# 3310USBC-1.net
KiCad netlist of a schematic drawn in EasyEDA Pro
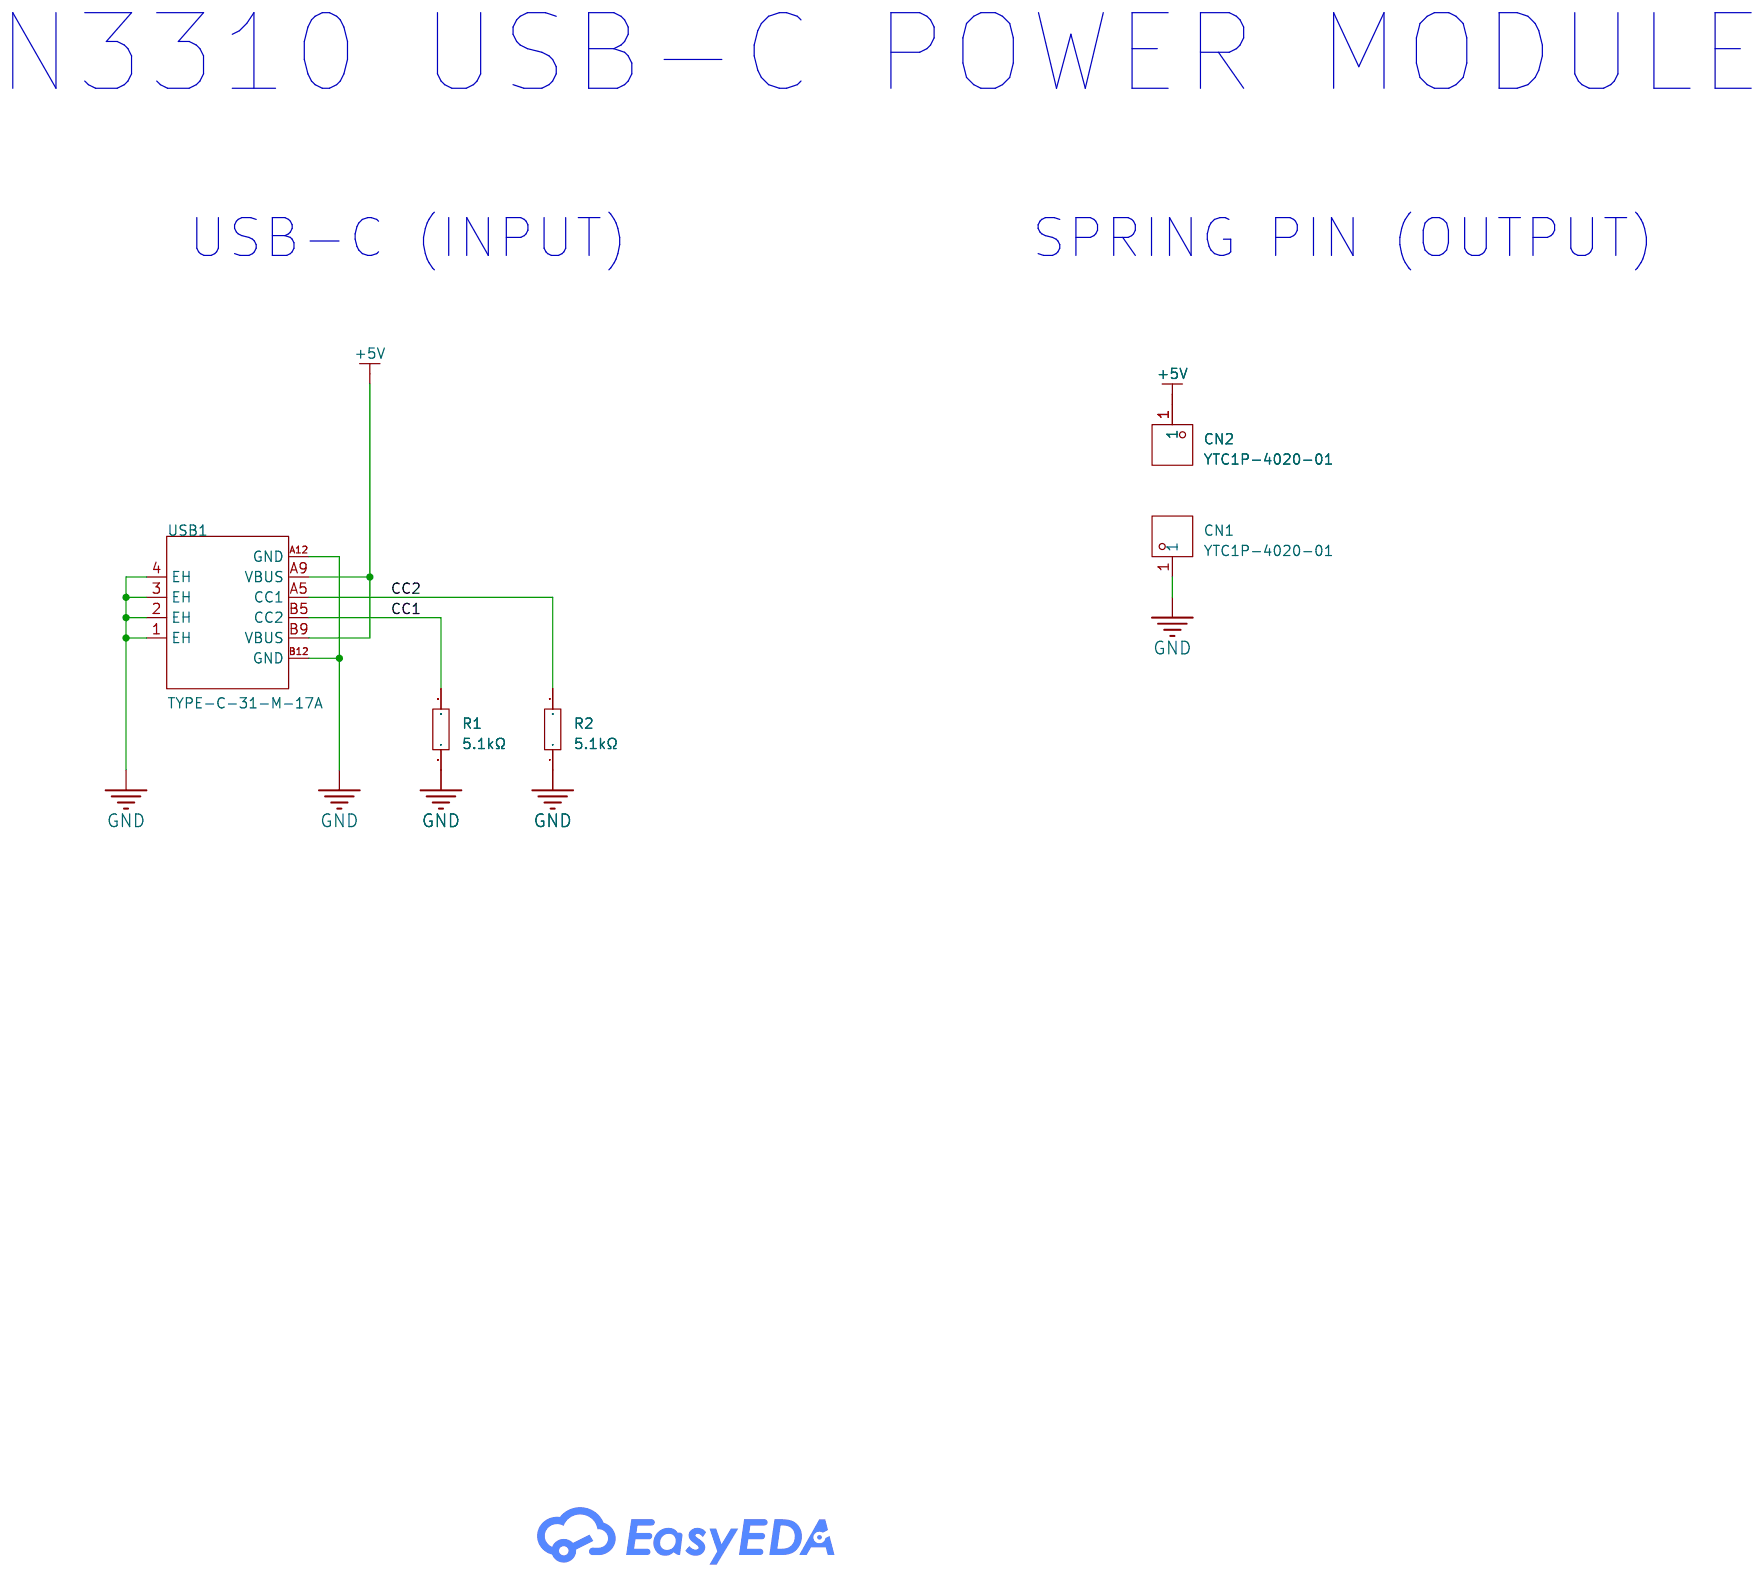
[diagram p0: schematic sheet]

(export (version "E")
  (design (tool "Eeschema 10.0.6"))
  (components
    (comp (ref "CN1")
      (value "YTC1P-4020-01")
      (footprint "easyedapro:TESTPOINT-SMD_BD2.0_YTC1P-4020-01")
      (fields (field (name "Manufacturer") "YIYUAN(怡远)"))
      (libsource (lib "easyedapro") (part "YTC1P-4020-01"))
    )
    (comp (ref "CN2")
      (value "YTC1P-4020-01")
      (footprint "easyedapro:TESTPOINT-SMD_BD2.0_YTC1P-4020-01")
      (fields (field (name "Manufacturer") "YIYUAN(怡远)"))
      (libsource (lib "easyedapro") (part "YTC1P-4020-01"))
    )
    (comp (ref "R1")
      (value "5.1kΩ")
      (footprint "easyedapro:R0805")
      (fields
        (field (name "Manufacturer Part") "0805W8F5101T5E")
        (field (name "Manufacturer") "UNI-ROYAL(厚声)")
      )
      (libsource (lib "easyedapro") (part "0805W8F5101T5E"))
    )
    (comp (ref "R2")
      (value "5.1kΩ")
      (footprint "easyedapro:R0805")
      (fields
        (field (name "Manufacturer Part") "0805W8F5101T5E")
        (field (name "Manufacturer") "UNI-ROYAL(厚声)")
      )
      (libsource (lib "easyedapro") (part "0805W8F5101T5E"))
    )
    (comp (ref "USB1")
      (value "TYPE-C-31-M-17A")
      (footprint "easyedapro:TYPE-C-SMD_TYPE-C-31-M-17A")
      (fields (field (name "Manufacturer") "韩国韩荣"))
      (libsource (lib "easyedapro") (part "TYPE-C-31-M-17A"))
    )
  )
  (nets
    (net (code "1") (name "+5V") (class "Default")
      (node (ref "CN2") (pin "1") (pinfunction "1_1") (pintype "unspecified"))
      (node (ref "USB1") (pin "A9") (pinfunction "VBUS_A9") (pintype "unspecified"))
      (node (ref "USB1") (pin "B9") (pinfunction "VBUS_B9") (pintype "unspecified"))
    )
    (net (code "2") (name "/CC1") (class "Default")
      (node (ref "R1") (pin "2") (pinfunction "2_2") (pintype "input"))
      (node (ref "USB1") (pin "B5") (pinfunction "CC2_B5") (pintype "unspecified"))
    )
    (net (code "3") (name "/CC2") (class "Default")
      (node (ref "R2") (pin "2") (pinfunction "2_2") (pintype "input"))
      (node (ref "USB1") (pin "A5") (pinfunction "CC1_A5") (pintype "unspecified"))
    )
    (net (code "4") (name "GND") (class "Default")
      (node (ref "CN1") (pin "1") (pinfunction "1_1") (pintype "unspecified"))
      (node (ref "R1") (pin "1") (pinfunction "1_1") (pintype "input"))
      (node (ref "R2") (pin "1") (pinfunction "1_1") (pintype "input"))
      (node (ref "USB1") (pin "1") (pinfunction "EH_1") (pintype "unspecified"))
      (node (ref "USB1") (pin "2") (pinfunction "EH_2") (pintype "unspecified"))
      (node (ref "USB1") (pin "3") (pinfunction "EH_3") (pintype "unspecified"))
      (node (ref "USB1") (pin "4") (pinfunction "EH_4") (pintype "unspecified"))
      (node (ref "USB1") (pin "A12") (pinfunction "GND_A12") (pintype "unspecified"))
      (node (ref "USB1") (pin "B12") (pinfunction "GND_B12") (pintype "unspecified"))
    )
  )
)
